# Power.net
KiCad netlist of a schematic drawn in Altium Designer
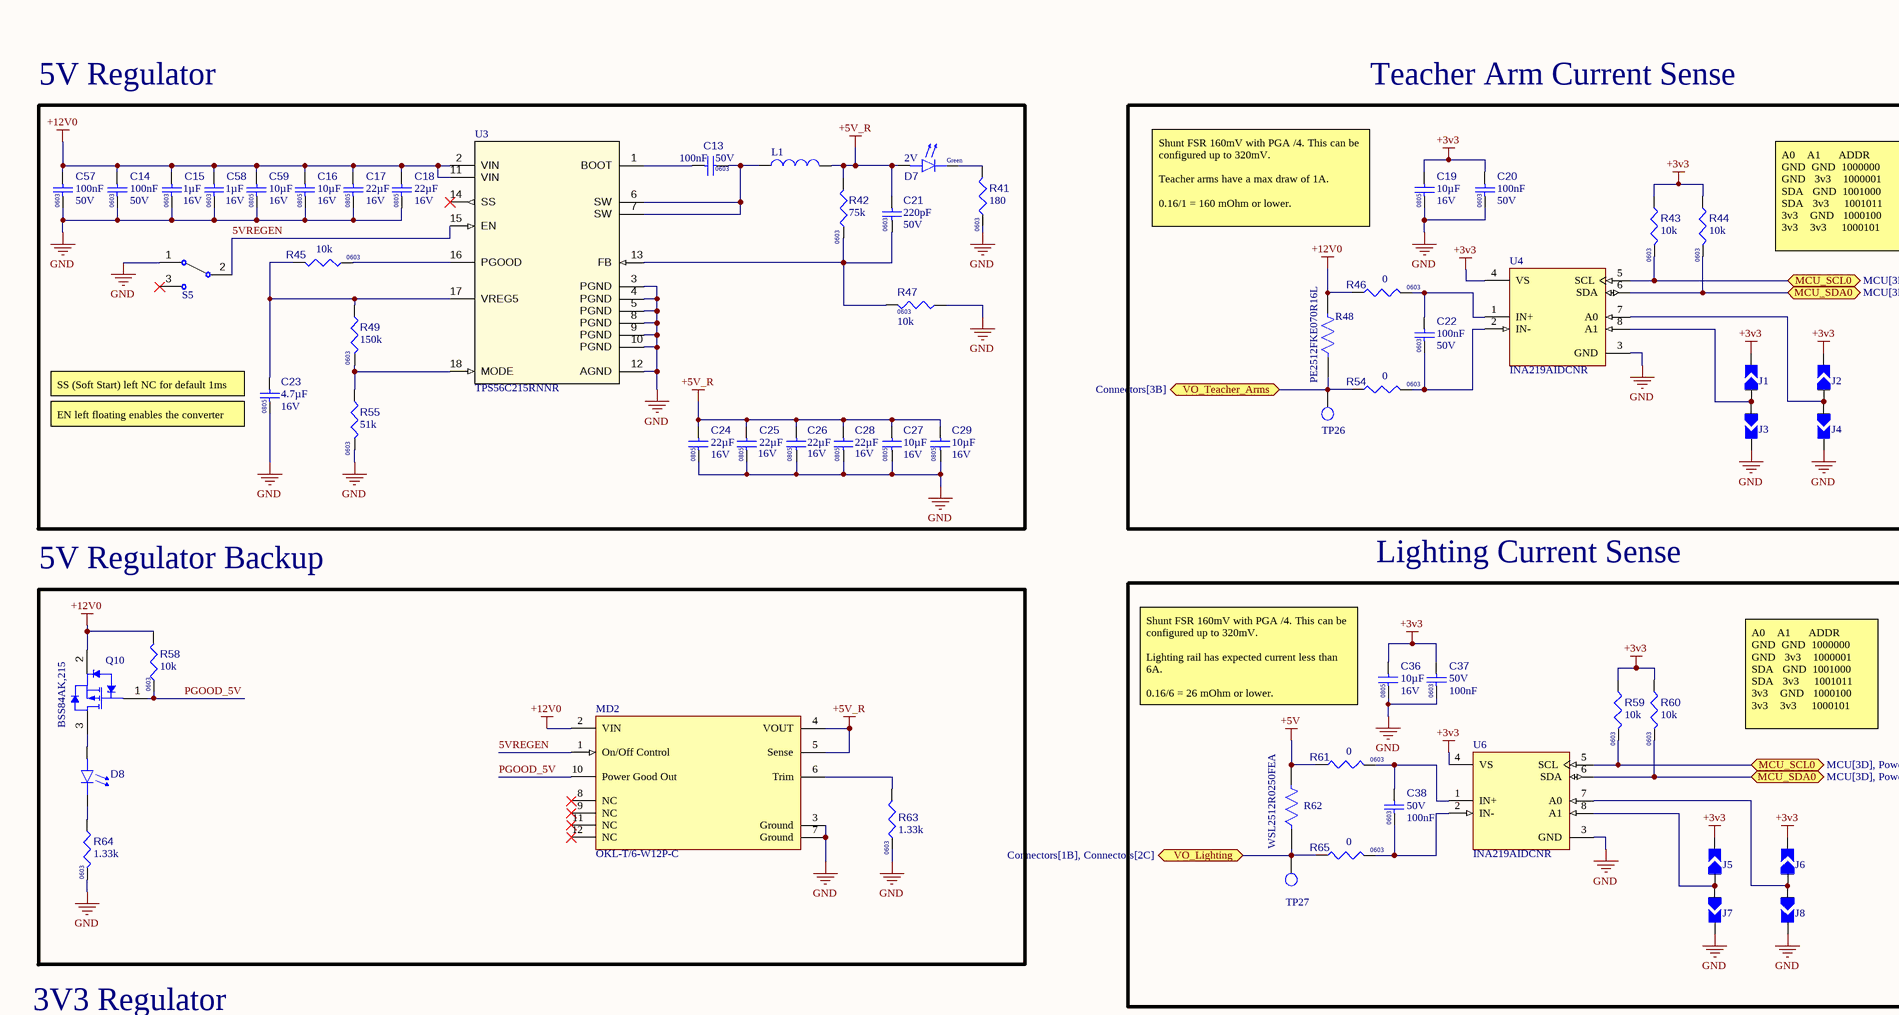
[diagram p0: Power.SchDoc, top left]
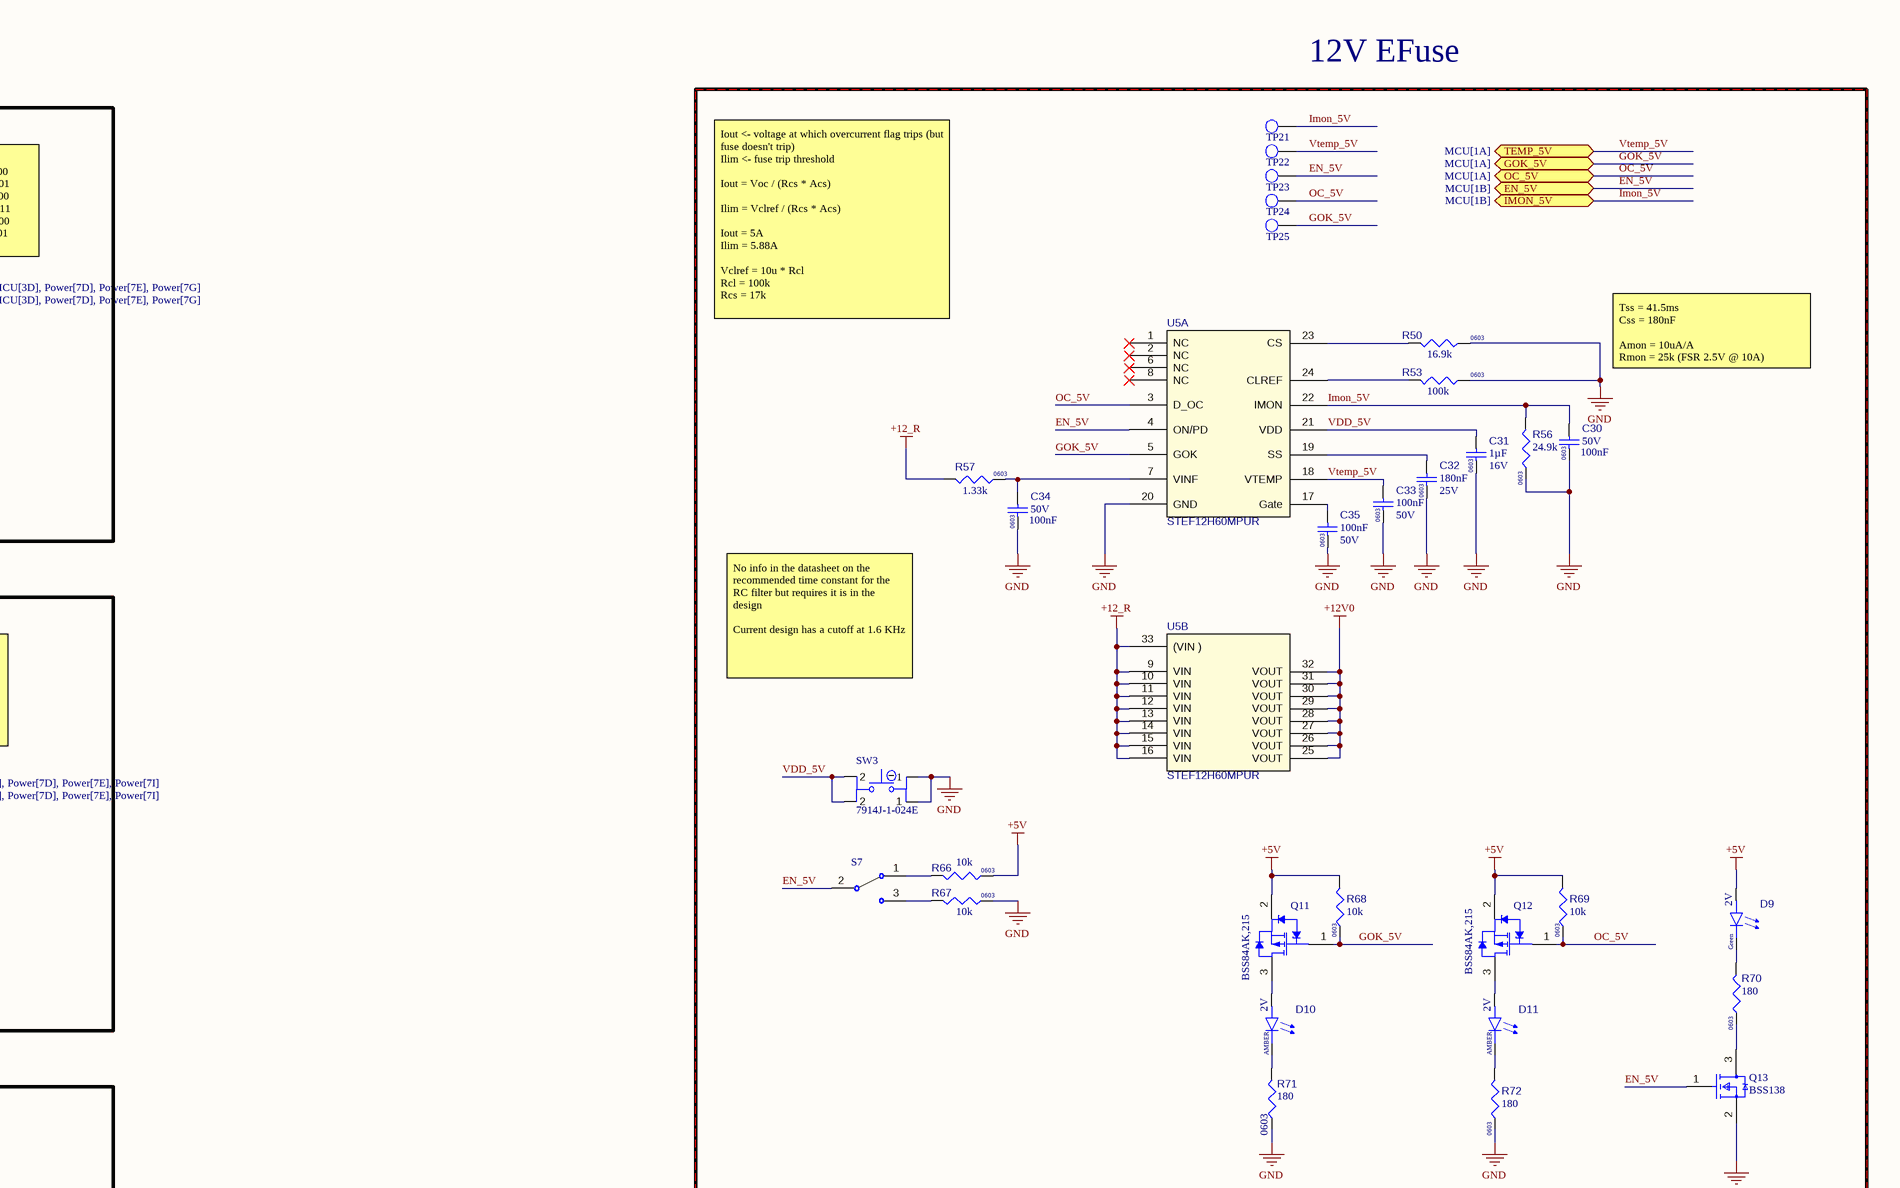
[diagram p1: Power.SchDoc, top right]
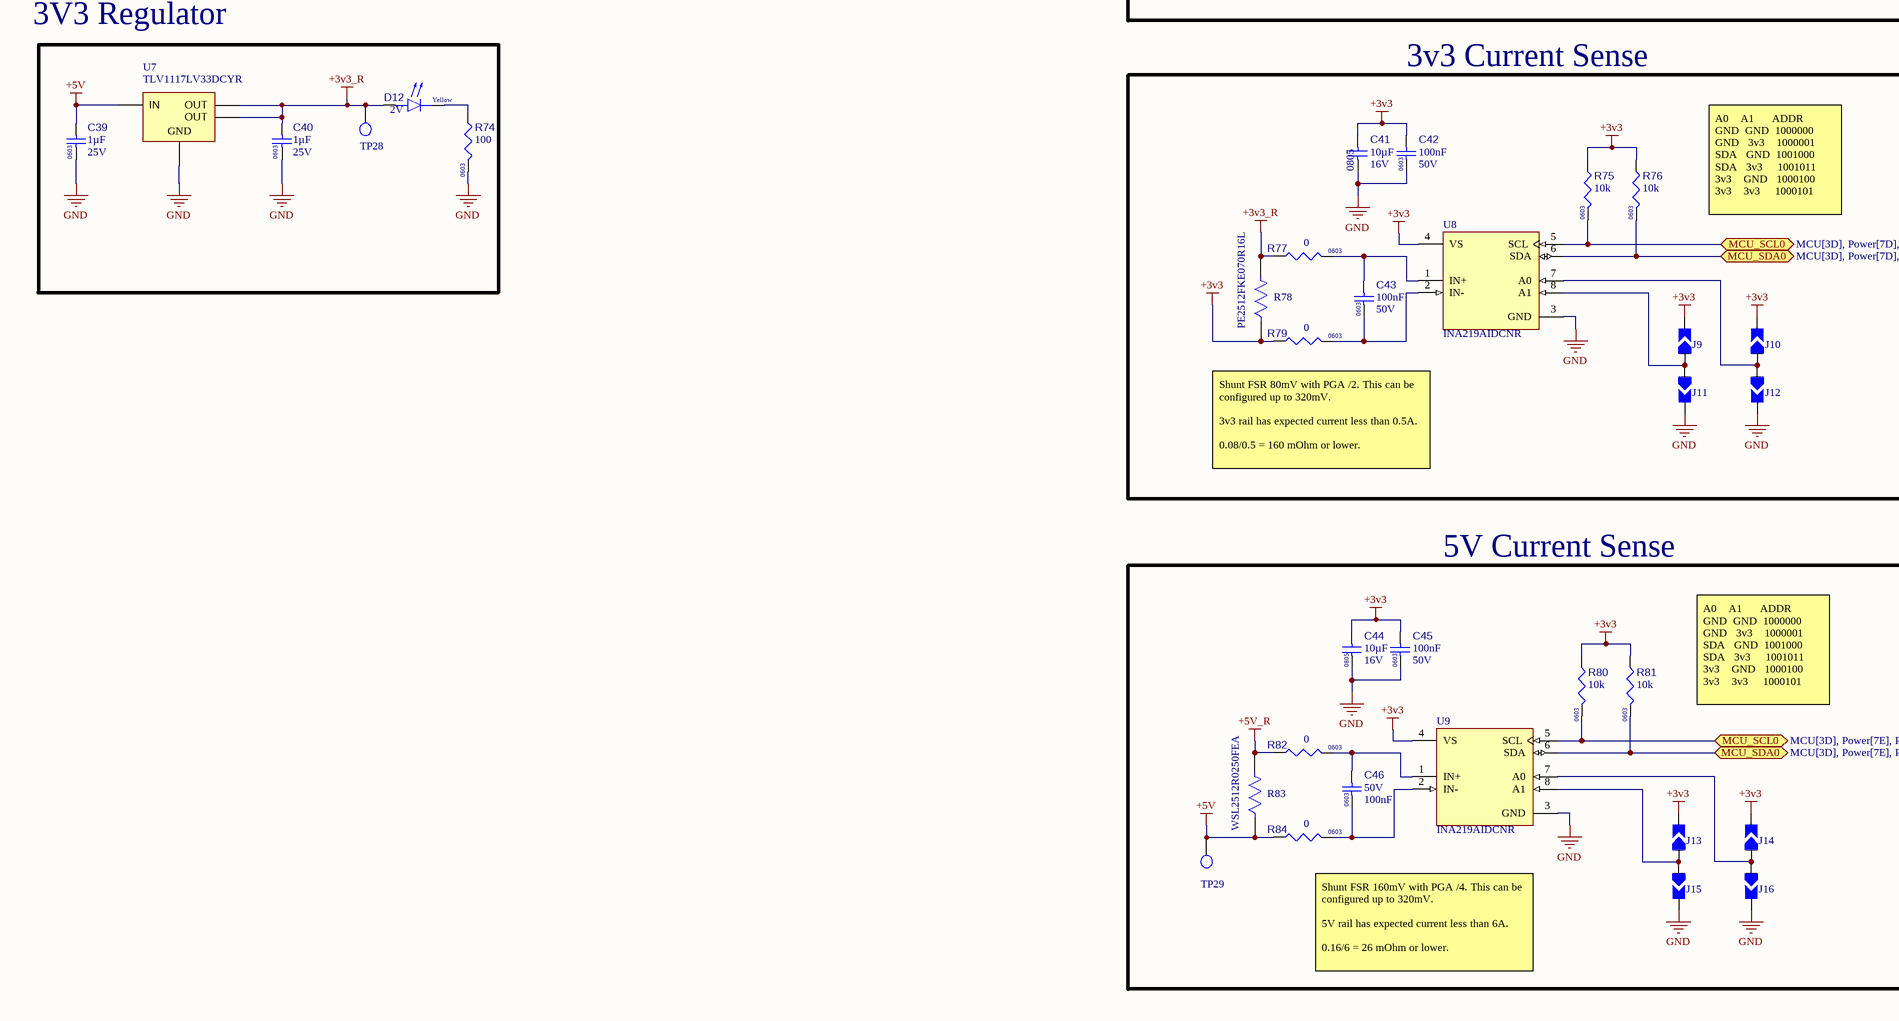
[diagram p2: Power.SchDoc, bottom left]

(export (version "E")
  (design (tool "Eeschema 10.0.6"))
  (components
    (comp (ref "C13")
      (value "100nF")
      (footprint "CAPC1608X90X40NL10T20")
      (description "Chip Capacitor, 100 nF, +/- 10%, 50 V, 0603 (1608 Metric)")
      (fields
        (field (name "TOLERANCE") "10%")
        (field (name "VOLTAGE RATING") "50V")
        (field (name "CASE/PACKAGE") "0603")
        (field (name "Comment") "Capacitor 100 nF +/-10% 50 V 0603")
      )
      (libsource (lib "hawaiirobotics") (part "CAP-NP-2"))
    )
    (comp (ref "C14")
      (value "100nF")
      (footprint "CAPC1608X90X40NL10T20")
      (description "Chip Capacitor, 100 nF, +/- 10%, 50 V, 0603 (1608 Metric)")
      (fields
        (field (name "TOLERANCE") "10%")
        (field (name "VOLTAGE RATING") "50V")
        (field (name "CASE/PACKAGE") "0603")
        (field (name "Comment") "Capacitor 100 nF +/-10% 50 V 0603")
      )
      (libsource (lib "hawaiirobotics") (part "CAP-NP-2"))
    )
    (comp (ref "C15")
      (value "1µF")
      (footprint "CAPC1608X90X35NL15T15")
      (description "Chip Capacitor, 1 uF, +/- 10%, 16 V, 0603 (1608 Metric)")
      (fields
        (field (name "CASE/PACKAGE") "0603")
        (field (name "VOLTAGE RATING") "16V")
        (field (name "TOLERANCE") "10%")
        (field (name "Comment") "Capacitor 1uF +/- 10% 16V 0603")
      )
      (libsource (lib "hawaiirobotics") (part "CAP-NP-2"))
    )
    (comp (ref "C16")
      (value "10µF")
      (footprint "CAP CER 10UF 16V X5R 0805-Footprint-1")
      (fields
        (field (name "VOLTAGE RATING") "16V")
        (field (name "CASE/PACKAGE") "0805")
        (field (name "Comment") "CAP CER 10UF 16V X5R 0805")
      )
      (libsource (lib "hawaiirobotics") (part "CAP-NP-2"))
    )
    (comp (ref "C17")
      (value "22µF")
      (footprint "CL21A226MOQNNNE-Footprint-1")
      (fields
        (field (name "VOLTAGE RATING") "16V")
        (field (name "CASE/PACKAGE") "0805")
        (field (name "Comment") "CL21A226MOQNNNE")
      )
      (libsource (lib "hawaiirobotics") (part "CAP-NP-2"))
    )
    (comp (ref "C18")
      (value "22µF")
      (footprint "CL21A226MOQNNNE-Footprint-1")
      (fields
        (field (name "VOLTAGE RATING") "16V")
        (field (name "CASE/PACKAGE") "0805")
        (field (name "Comment") "CL21A226MOQNNNE")
      )
      (libsource (lib "hawaiirobotics") (part "CAP-NP-2"))
    )
    (comp (ref "C19")
      (value "10µF")
      (footprint "CAP CER 10UF 16V X5R 0805-Footprint-1")
      (fields
        (field (name "VOLTAGE RATING") "16V")
        (field (name "CASE/PACKAGE") "0805")
        (field (name "Comment") "CAP CER 10UF 16V X5R 0805")
      )
      (libsource (lib "hawaiirobotics") (part "CAP-NP-2"))
    )
    (comp (ref "C20")
      (value "100nF")
      (footprint "CAPC1608X90X40NL10T20")
      (description "Chip Capacitor, 100 nF, +/- 10%, 50 V, 0603 (1608 Metric)")
      (fields
        (field (name "TOLERANCE") "10%")
        (field (name "VOLTAGE RATING") "50V")
        (field (name "CASE/PACKAGE") "0603")
        (field (name "Comment") "Capacitor 100 nF +/-10% 50 V 0603")
      )
      (libsource (lib "hawaiirobotics") (part "CAP-NP-2"))
    )
    (comp (ref "C21")
      (value "220pF")
      (footprint "FP-CL10-IPC_B")
      (fields
        (field (name "RATED DC VOLTAGE (URDC)") "50V")
        (field (name "CASE/PACKAGE") "0603")
        (field (name "Comment") "CL10C221JB8NNNC")
      )
      (libsource (lib "hawaiirobotics") (part "CAP-NP-2"))
    )
    (comp (ref "C22")
      (value "100nF")
      (footprint "CAPC1608X90X40NL10T20")
      (description "Chip Capacitor, 100 nF, +/- 10%, 50 V, 0603 (1608 Metric)")
      (fields
        (field (name "TOLERANCE") "10%")
        (field (name "VOLTAGE RATING") "50V")
        (field (name "CASE/PACKAGE") "0603")
        (field (name "Comment") "Capacitor 100 nF +/-10% 50 V 0603")
      )
      (libsource (lib "hawaiirobotics") (part "CAP-NP-2"))
    )
    (comp (ref "C23")
      (value "4.7µF")
      (footprint "CL21A475KOFNNNE-Footprint-1")
      (fields
        (field (name "CASE/PACKAGE") "0805")
        (field (name "RATED DC VOLTAGE (URDC)") "16V")
        (field (name "Comment") "CL21A475KOFNNNE")
      )
      (libsource (lib "hawaiirobotics") (part "CAP-NP-2"))
    )
    (comp (ref "C24")
      (value "22µF")
      (footprint "CL21A226MOQNNNE-Footprint-1")
      (fields
        (field (name "VOLTAGE RATING") "16V")
        (field (name "CASE/PACKAGE") "0805")
        (field (name "Comment") "CL21A226MOQNNNE")
      )
      (libsource (lib "hawaiirobotics") (part "CAP-NP-2"))
    )
    (comp (ref "C25")
      (value "22µF")
      (footprint "CL21A226MOQNNNE-Footprint-1")
      (fields
        (field (name "VOLTAGE RATING") "16V")
        (field (name "CASE/PACKAGE") "0805")
        (field (name "Comment") "CL21A226MOQNNNE")
      )
      (libsource (lib "hawaiirobotics") (part "CAP-NP-2"))
    )
    (comp (ref "C26")
      (value "22µF")
      (footprint "CL21A226MOQNNNE-Footprint-1")
      (fields
        (field (name "VOLTAGE RATING") "16V")
        (field (name "CASE/PACKAGE") "0805")
        (field (name "Comment") "CL21A226MOQNNNE")
      )
      (libsource (lib "hawaiirobotics") (part "CAP-NP-2"))
    )
    (comp (ref "C27")
      (value "10µF")
      (footprint "CAP CER 10UF 16V X5R 0805-Footprint-1")
      (fields
        (field (name "VOLTAGE RATING") "16V")
        (field (name "CASE/PACKAGE") "0805")
        (field (name "Comment") "CAP CER 10UF 16V X5R 0805")
      )
      (libsource (lib "hawaiirobotics") (part "CAP-NP-2"))
    )
    (comp (ref "C28")
      (value "22µF")
      (footprint "CL21A226MOQNNNE-Footprint-1")
      (fields
        (field (name "VOLTAGE RATING") "16V")
        (field (name "CASE/PACKAGE") "0805")
        (field (name "Comment") "CL21A226MOQNNNE")
      )
      (libsource (lib "hawaiirobotics") (part "CAP-NP-2"))
    )
    (comp (ref "C29")
      (value "10µF")
      (footprint "CAP CER 10UF 16V X5R 0805-Footprint-1")
      (fields
        (field (name "VOLTAGE RATING") "16V")
        (field (name "CASE/PACKAGE") "0805")
        (field (name "Comment") "CAP CER 10UF 16V X5R 0805")
      )
      (libsource (lib "hawaiirobotics") (part "CAP-NP-2"))
    )
    (comp (ref "C30")
      (value "100nF")
      (footprint "CAPC1608X90X40NL10T20")
      (description "Chip Capacitor, 100 nF, +/- 10%, 50 V, 0603 (1608 Metric)")
      (fields
        (field (name "TOLERANCE") "10%")
        (field (name "VOLTAGE RATING") "50V")
        (field (name "CASE/PACKAGE") "0603")
        (field (name "Comment") "Capacitor 100 nF +/-10% 50 V 0603")
      )
      (libsource (lib "hawaiirobotics") (part "CAP-NP-2"))
    )
    (comp (ref "C31")
      (value "1µF")
      (footprint "CAPC1608X90X35NL15T15")
      (description "Chip Capacitor, 1 uF, +/- 10%, 16 V, 0603 (1608 Metric)")
      (fields
        (field (name "CASE/PACKAGE") "0603")
        (field (name "TOLERANCE") "10%")
        (field (name "VOLTAGE RATING") "16V")
        (field (name "Comment") "Capacitor 1uF +/- 10% 16V 0603")
      )
      (libsource (lib "hawaiirobotics") (part "CAP-NP-2"))
    )
    (comp (ref "C32")
      (value "180nF")
      (footprint "FP-GCM188-0_1-IPC_C")
      (fields
        (field (name "CASE/PACKAGE") "0603")
        (field (name "RATED DC VOLTAGE (URDC)") "25V")
        (field (name "Comment") "GCM188R71E184KA55D")
      )
      (libsource (lib "hawaiirobotics") (part "CAP-NP-2"))
    )
    (comp (ref "C33")
      (value "100nF")
      (footprint "CAPC1608X90X40NL10T20")
      (description "Chip Capacitor, 100 nF, +/- 10%, 50 V, 0603 (1608 Metric)")
      (fields
        (field (name "TOLERANCE") "10%")
        (field (name "VOLTAGE RATING") "50V")
        (field (name "CASE/PACKAGE") "0603")
        (field (name "Comment") "Capacitor 100 nF +/-10% 50 V 0603")
      )
      (libsource (lib "hawaiirobotics") (part "CAP-NP-2"))
    )
    (comp (ref "C34")
      (value "100nF")
      (footprint "CAPC1608X90X40NL10T20")
      (description "Chip Capacitor, 100 nF, +/- 10%, 50 V, 0603 (1608 Metric)")
      (fields
        (field (name "TOLERANCE") "10%")
        (field (name "VOLTAGE RATING") "50V")
        (field (name "CASE/PACKAGE") "0603")
        (field (name "Comment") "Capacitor 100 nF +/-10% 50 V 0603")
      )
      (libsource (lib "hawaiirobotics") (part "CAP-NP-2"))
    )
    (comp (ref "C35")
      (value "100nF")
      (footprint "CAPC1608X90X40NL10T20")
      (description "Chip Capacitor, 100 nF, +/- 10%, 50 V, 0603 (1608 Metric)")
      (fields
        (field (name "TOLERANCE") "10%")
        (field (name "VOLTAGE RATING") "50V")
        (field (name "CASE/PACKAGE") "0603")
        (field (name "Comment") "Capacitor 100 nF +/-10% 50 V 0603")
      )
      (libsource (lib "hawaiirobotics") (part "CAP-NP-2"))
    )
    (comp (ref "C36")
      (value "10µF")
      (footprint "CAP CER 10UF 16V X5R 0805-Footprint-1")
      (fields
        (field (name "VOLTAGE RATING") "16V")
        (field (name "CASE/PACKAGE") "0805")
        (field (name "Comment") "CAP CER 10UF 16V X5R 0805")
      )
      (libsource (lib "hawaiirobotics") (part "CAP-NP-2"))
    )
    (comp (ref "C37")
      (value "100nF")
      (footprint "CAPC1608X90X40NL10T20")
      (description "Chip Capacitor, 100 nF, +/- 10%, 50 V, 0603 (1608 Metric)")
      (fields
        (field (name "TOLERANCE") "10%")
        (field (name "VOLTAGE RATING") "50V")
        (field (name "CASE/PACKAGE") "0603")
        (field (name "Comment") "Capacitor 100 nF +/-10% 50 V 0603")
      )
      (libsource (lib "hawaiirobotics") (part "CAP-NP-2"))
    )
    (comp (ref "C38")
      (value "100nF")
      (footprint "CAPC1608X90X40NL10T20")
      (description "Chip Capacitor, 100 nF, +/- 10%, 50 V, 0603 (1608 Metric)")
      (fields
        (field (name "TOLERANCE") "10%")
        (field (name "VOLTAGE RATING") "50V")
        (field (name "CASE/PACKAGE") "0603")
        (field (name "Comment") "Capacitor 100 nF +/-10% 50 V 0603")
      )
      (libsource (lib "hawaiirobotics") (part "CAP-NP-2"))
    )
    (comp (ref "C39")
      (value "1µF")
      (footprint "FP-CL10-IPC_B")
      (fields
        (field (name "RATED DC VOLTAGE (URDC)") "25V")
        (field (name "CASE/PACKAGE") "0603")
        (field (name "Comment") "CL10B105KA8NNNC")
      )
      (libsource (lib "hawaiirobotics") (part "CAP-NP-2"))
    )
    (comp (ref "C40")
      (value "1µF")
      (footprint "FP-CL10-IPC_B")
      (fields
        (field (name "RATED DC VOLTAGE (URDC)") "25V")
        (field (name "CASE/PACKAGE") "0603")
        (field (name "Comment") "CL10B105KA8NNNC")
      )
      (libsource (lib "hawaiirobotics") (part "CAP-NP-2"))
    )
    (comp (ref "C41")
      (value "10µF")
      (footprint "CAP CER 10UF 16V X5R 0805-Footprint-1")
      (fields
        (field (name "VOLTAGE RATING") "16V")
        (field (name "CASE/PACKAGE") "0805")
        (field (name "Comment") "CAP CER 10UF 16V X5R 0805")
      )
      (libsource (lib "hawaiirobotics") (part "CAP-NP-2"))
    )
    (comp (ref "C42")
      (value "100nF")
      (footprint "CAPC1608X90X40NL10T20")
      (description "Chip Capacitor, 100 nF, +/- 10%, 50 V, 0603 (1608 Metric)")
      (fields
        (field (name "TOLERANCE") "10%")
        (field (name "VOLTAGE RATING") "50V")
        (field (name "CASE/PACKAGE") "0603")
        (field (name "Comment") "Capacitor 100 nF +/-10% 50 V 0603")
      )
      (libsource (lib "hawaiirobotics") (part "CAP-NP-2"))
    )
    (comp (ref "C43")
      (value "100nF")
      (footprint "CAPC1608X90X40NL10T20")
      (description "Chip Capacitor, 100 nF, +/- 10%, 50 V, 0603 (1608 Metric)")
      (fields
        (field (name "TOLERANCE") "10%")
        (field (name "VOLTAGE RATING") "50V")
        (field (name "CASE/PACKAGE") "0603")
        (field (name "Comment") "Capacitor 100 nF +/-10% 50 V 0603")
      )
      (libsource (lib "hawaiirobotics") (part "CAP-NP-2"))
    )
    (comp (ref "C44")
      (value "10µF")
      (footprint "CAP CER 10UF 16V X5R 0805-Footprint-1")
      (fields
        (field (name "VOLTAGE RATING") "16V")
        (field (name "CASE/PACKAGE") "0805")
        (field (name "Comment") "CAP CER 10UF 16V X5R 0805")
      )
      (libsource (lib "hawaiirobotics") (part "CAP-NP-2"))
    )
    (comp (ref "C45")
      (value "100nF")
      (footprint "CAPC1608X90X40NL10T20")
      (description "Chip Capacitor, 100 nF, +/- 10%, 50 V, 0603 (1608 Metric)")
      (fields
        (field (name "TOLERANCE") "10%")
        (field (name "VOLTAGE RATING") "50V")
        (field (name "CASE/PACKAGE") "0603")
        (field (name "Comment") "Capacitor 100 nF +/-10% 50 V 0603")
      )
      (libsource (lib "hawaiirobotics") (part "CAP-NP-2"))
    )
    (comp (ref "C46")
      (value "100nF")
      (footprint "CAPC1608X90X40NL10T20")
      (description "Chip Capacitor, 100 nF, +/- 10%, 50 V, 0603 (1608 Metric)")
      (fields
        (field (name "TOLERANCE") "10%")
        (field (name "VOLTAGE RATING") "50V")
        (field (name "CASE/PACKAGE") "0603")
        (field (name "Comment") "Capacitor 100 nF +/-10% 50 V 0603")
      )
      (libsource (lib "hawaiirobotics") (part "CAP-NP-2"))
    )
    (comp (ref "C57")
      (value "100nF")
      (footprint "CAPC1608X90X40NL10T20")
      (description "Chip Capacitor, 100 nF, +/- 10%, 50 V, 0603 (1608 Metric)")
      (fields
        (field (name "TOLERANCE") "10%")
        (field (name "VOLTAGE RATING") "50V")
        (field (name "CASE/PACKAGE") "0603")
        (field (name "Comment") "Capacitor 100 nF +/-10% 50 V 0603")
      )
      (libsource (lib "hawaiirobotics") (part "CAP-NP-2"))
    )
    (comp (ref "C58")
      (value "1µF")
      (footprint "CAPC1608X90X35NL15T15")
      (description "Chip Capacitor, 1 uF, +/- 10%, 16 V, 0603 (1608 Metric)")
      (fields
        (field (name "CASE/PACKAGE") "0603")
        (field (name "VOLTAGE RATING") "16V")
        (field (name "TOLERANCE") "10%")
        (field (name "Comment") "Capacitor 1uF +/- 10% 16V 0603")
      )
      (libsource (lib "hawaiirobotics") (part "CAP-NP-2"))
    )
    (comp (ref "C59")
      (value "10µF")
      (footprint "CAP CER 10UF 16V X5R 0805-Footprint-1")
      (fields
        (field (name "VOLTAGE RATING") "16V")
        (field (name "CASE/PACKAGE") "0805")
        (field (name "Comment") "CAP CER 10UF 16V X5R 0805")
      )
      (libsource (lib "hawaiirobotics") (part "CAP-NP-2"))
    )
    (comp (ref "D7")
      (value "150060VS75000")
      (footprint "WL-SMCW_0603_150060xx75000")
      (description "Single Color LED, Bright Green, Water Clear, 1.1mm")
      (fields (field (name "FORWARD VOLTAGE") "2V") (field (name "COLOR") "Green"))
      (libsource (lib "hawaiirobotics") (part "DIODE-LED-2"))
    )
    (comp (ref "D8")
      (value "150060RS75000")
      (footprint "WL-SMCW_0603_150060xx75000")
      (description "Single Color LED, Red, Water Clear, 1.1mm")
      (libsource (lib "hawaiirobotics") (part "DIODE-LED-2"))
    )
    (comp (ref "D9")
      (value "150060VS75000")
      (footprint "WL-SMCW_0603_150060xx75000")
      (description "Single Color LED, Bright Green, Water Clear, 1.1mm")
      (fields (field (name "FORWARD VOLTAGE") "2V") (field (name "COLOR") "Green"))
      (libsource (lib "hawaiirobotics") (part "DIODE-LED-2"))
    )
    (comp (ref "D10")
      (value "150060AS75000")
      (footprint "WL-SMCW_0603_150060xx75000")
      (description "Single Color LED, Amber, Water Clear, 1.1mm")
      (fields (field (name "FORWARD VOLTAGE") "2V") (field (name "COLOUR") "AMBER"))
      (libsource (lib "hawaiirobotics") (part "DIODE-LED-2"))
    )
    (comp (ref "D11")
      (value "150060AS75000")
      (footprint "WL-SMCW_0603_150060xx75000")
      (description "Single Color LED, Amber, Water Clear, 1.1mm")
      (fields (field (name "FORWARD VOLTAGE") "2V") (field (name "COLOUR") "AMBER"))
      (libsource (lib "hawaiirobotics") (part "DIODE-LED-2"))
    )
    (comp (ref "D12")
      (value "150060YS75000")
      (footprint "WL-SMCW_0603_150060xx75000")
      (description "Single Color LED, Yellow, Water Clear, 1.1mm")
      (fields (field (name "FORWARD VOLTAGE") "2V") (field (name "COLOR") "Yellow"))
      (libsource (lib "hawaiirobotics") (part "DIODE-LED-2"))
    )
    (comp (ref "J1")
      (value "Solder jumper")
      (footprint "New footprint 1")
      (libsource (lib "hawaiirobotics") (part "New symbol 1"))
    )
    (comp (ref "J2")
      (value "Solder jumper")
      (footprint "New footprint 1")
      (libsource (lib "hawaiirobotics") (part "New symbol 1"))
    )
    (comp (ref "J3")
      (value "Solder jumper")
      (footprint "New footprint 1")
      (libsource (lib "hawaiirobotics") (part "New symbol 1"))
    )
    (comp (ref "J4")
      (value "Solder jumper")
      (footprint "New footprint 1")
      (libsource (lib "hawaiirobotics") (part "New symbol 1"))
    )
    (comp (ref "J5")
      (value "Solder jumper")
      (footprint "New footprint 1")
      (libsource (lib "hawaiirobotics") (part "New symbol 1"))
    )
    (comp (ref "J6")
      (value "Solder jumper")
      (footprint "New footprint 1")
      (libsource (lib "hawaiirobotics") (part "New symbol 1"))
    )
    (comp (ref "J7")
      (value "Solder jumper")
      (footprint "New footprint 1")
      (libsource (lib "hawaiirobotics") (part "New symbol 1"))
    )
    (comp (ref "J8")
      (value "Solder jumper")
      (footprint "New footprint 1")
      (libsource (lib "hawaiirobotics") (part "New symbol 1"))
    )
    (comp (ref "J9")
      (value "Solder jumper")
      (footprint "New footprint 1")
      (libsource (lib "hawaiirobotics") (part "New symbol 1"))
    )
    (comp (ref "J10")
      (value "Solder jumper")
      (footprint "New footprint 1")
      (libsource (lib "hawaiirobotics") (part "New symbol 1"))
    )
    (comp (ref "J11")
      (value "Solder jumper")
      (footprint "New footprint 1")
      (libsource (lib "hawaiirobotics") (part "New symbol 1"))
    )
    (comp (ref "J12")
      (value "Solder jumper")
      (footprint "New footprint 1")
      (libsource (lib "hawaiirobotics") (part "New symbol 1"))
    )
    (comp (ref "J13")
      (value "Solder jumper")
      (footprint "New footprint 1")
      (libsource (lib "hawaiirobotics") (part "New symbol 1"))
    )
    (comp (ref "J14")
      (value "Solder jumper")
      (footprint "New footprint 1")
      (libsource (lib "hawaiirobotics") (part "New symbol 1"))
    )
    (comp (ref "J15")
      (value "Solder jumper")
      (footprint "New footprint 1")
      (libsource (lib "hawaiirobotics") (part "New symbol 1"))
    )
    (comp (ref "J16")
      (value "Solder jumper")
      (footprint "New footprint 1")
      (libsource (lib "hawaiirobotics") (part "New symbol 1"))
    )
    (comp (ref "L1")
      (value "744325330")
      (footprint "WE-HCI_1050")
      (description "General Purpose Inductor, 3.3uH, 20%, 1 Element, SMD, 4140")
      (fields (field (name "TOLERANCE") "20%"))
      (libsource (lib "hawaiirobotics") (part "IND-2"))
    )
    (comp (ref "MD2")
      (value "OKL-T/6-W12P-C")
      (footprint "FP-OKL-T-6-W12-MFG")
      (description "DC DC CONVERTER 0.591-5.5V 30W")
      (libsource (lib "Altium Content Vault") (part "54782e8334bb74e7d5378ece10d419b"))
    )
    (comp (ref "Q10")
      (value "BSS84AK,215")
      (footprint "NXP-SOT23_N")
      (description "P-Channel Trench MOSFET, -50 V, -0.18 A, -55 to 150 degC, 3-Pin SOT23, Tape and Reel")
      (fields (field (name "MANUFACTURER") "NXP Semiconductors"))
      (libsource (lib "Altium Content Vault") (part "NXP-PMOS-GSD-3_B"))
    )
    (comp (ref "Q11")
      (value "BSS84AK,215")
      (footprint "NXP-SOT23_N")
      (description "P-Channel Trench MOSFET, -50 V, -0.18 A, -55 to 150 degC, 3-Pin SOT23, Tape and Reel")
      (fields (field (name "MANUFACTURER") "NXP Semiconductors"))
      (libsource (lib "Altium Content Vault") (part "NXP-PMOS-GSD-3_B"))
    )
    (comp (ref "Q12")
      (value "BSS84AK,215")
      (footprint "NXP-SOT23_N")
      (description "P-Channel Trench MOSFET, -50 V, -0.18 A, -55 to 150 degC, 3-Pin SOT23, Tape and Reel")
      (fields (field (name "MANUFACTURER") "NXP Semiconductors"))
      (libsource (lib "Altium Content Vault") (part "NXP-PMOS-GSD-3_B"))
    )
    (comp (ref "Q13")
      (value "BSS138")
      (footprint "FP-318-08-IPC_B")
      (description "MOSFET N-CH 50V 220MA SOT-23")
      (libsource (lib "Altium Content Vault") (part "3b9c635fedb024a5347a57b145af9cc"))
    )
    (comp (ref "R41")
      (value "180")
      (footprint "RESC0603(1608)_N")
      (fields
        (field (name "TOLERANCE") "5%")
        (field (name "CASE/PACKAGE") "0603")
        (field (name "POWER") "100mW")
        (field (name "Comment") "RC0603JR-07180RL")
      )
      (libsource (lib "hawaiirobotics") (part "RES-2"))
    )
    (comp (ref "R42")
      (value "75k")
      (footprint "RC0603JR-0720KL-Footprint-1")
      (fields
        (field (name "TOLERANCE") "1%")
        (field (name "POWER") "100mW")
        (field (name "CASE/PACKAGE") "0603")
        (field (name "Comment") "RC0603FR-0775KL")
      )
      (libsource (lib "hawaiirobotics") (part "RES-2"))
    )
    (comp (ref "R43")
      (value "10k")
      (footprint "RESC1608X55X25NL10T15")
      (description "Chip Resistor, 10 KOhm, +/- 1%, 01 W, -55 to 155 degC, 0603 (1608 Metric)")
      (fields
        (field (name "CASE/PACKAGE") "0603")
        (field (name "POWER") "100mW")
        (field (name "TOLERANCE") "1%")
      )
      (libsource (lib "hawaiirobotics") (part "RES-2"))
    )
    (comp (ref "R44")
      (value "10k")
      (footprint "RESC1608X55X25NL10T15")
      (description "Chip Resistor, 10 KOhm, +/- 1%, 01 W, -55 to 155 degC, 0603 (1608 Metric)")
      (fields
        (field (name "CASE/PACKAGE") "0603")
        (field (name "POWER") "100mW")
        (field (name "TOLERANCE") "1%")
      )
      (libsource (lib "hawaiirobotics") (part "RES-2"))
    )
    (comp (ref "R45")
      (value "10k")
      (footprint "RESC1608X55X25NL10T15")
      (description "Chip Resistor, 10 KOhm, +/- 1%, 01 W, -55 to 155 degC, 0603 (1608 Metric)")
      (fields
        (field (name "CASE/PACKAGE") "0603")
        (field (name "POWER") "100mW")
        (field (name "TOLERANCE") "1%")
      )
      (libsource (lib "hawaiirobotics") (part "RES-2"))
    )
    (comp (ref "R46")
      (value "0")
      (footprint "RC0603JR-0720KL-Footprint-1")
      (description "Metal Glaze/thick Film, 0.1W, 0ohm, Surface Mount, 0603")
      (fields
        (field (name "CASE/PACKAGE") "0603")
        (field (name "TOLERANCE") "1%")
        (field (name "POWER") "100mW")
      )
      (libsource (lib "hawaiirobotics") (part "RES-2"))
    )
    (comp (ref "R47")
      (value "10k")
      (footprint "RESC1608X55X25NL10T15")
      (description "Chip Resistor, 10 KOhm, +/- 1%, 01 W, -55 to 155 degC, 0603 (1608 Metric)")
      (fields
        (field (name "CASE/PACKAGE") "0603")
        (field (name "POWER") "100mW")
        (field (name "TOLERANCE") "1%")
      )
      (libsource (lib "hawaiirobotics") (part "RES-2"))
    )
    (comp (ref "R48")
      (value "PE2512FKE070R16L")
      (footprint "FP-WSL2512-0_762-IPC_B")
      (description "Resistor Current Sense Metal Film 2512 160mOhm ±1% 1W ±50ppm/°C T/R Automotive")
      (libsource (lib "hawaiirobotics") (part "1029c3af85768c4190bb7ad29bc67b5"))
    )
    (comp (ref "R49")
      (value "150k")
      (footprint "RC0603JR-0720KL-Footprint-1")
      (fields
        (field (name "CASE/PACKAGE") "0603")
        (field (name "TOLERANCE") "1%")
        (field (name "POWER") "100mW")
        (field (name "Comment") "RC0603FR-13150KL")
      )
      (libsource (lib "hawaiirobotics") (part "RES-2"))
    )
    (comp (ref "R50")
      (value "16.9k")
      (footprint "RESC1608X55X25NL10T15")
      (fields
        (field (name "CASE/PACKAGE") "0603")
        (field (name "TOLERANCE") "1%")
        (field (name "POWER") "100mW")
        (field (name "Comment") "RC0603FR-0716K9L")
      )
      (libsource (lib "hawaiirobotics") (part "RES-2"))
    )
    (comp (ref "R53")
      (value "100k")
      (footprint "RESC1608X55X25NL10T15")
      (fields
        (field (name "POWER") "100mW")
        (field (name "TOLERANCE") "1%")
        (field (name "CASE/PACKAGE") "0603")
        (field (name "Comment") "RC0603FR-07100KL")
      )
      (libsource (lib "hawaiirobotics") (part "RES-2"))
    )
    (comp (ref "R54")
      (value "0")
      (footprint "RC0603JR-0720KL-Footprint-1")
      (description "Metal Glaze/thick Film, 0.1W, 0ohm, Surface Mount, 0603")
      (fields
        (field (name "CASE/PACKAGE") "0603")
        (field (name "TOLERANCE") "1%")
        (field (name "POWER") "100mW")
      )
      (libsource (lib "hawaiirobotics") (part "RES-2"))
    )
    (comp (ref "R55")
      (value "51k")
      (footprint "RC0603JR-0720KL-Footprint-1")
      (fields
        (field (name "TOLERANCE") "1%")
        (field (name "CASE/PACKAGE") "0603")
        (field (name "POWER") "100mW")
        (field (name "Comment") "RC0603FR-0751KL")
      )
      (libsource (lib "hawaiirobotics") (part "RES-2"))
    )
    (comp (ref "R56")
      (value "24.9k")
      (footprint "RESC1608X55X25NL10T15")
      (fields
        (field (name "POWER") "100mW")
        (field (name "TOLERANCE") "1%")
        (field (name "CASE/PACKAGE") "0603")
        (field (name "Comment") "RC0603FR-1024K9L")
      )
      (libsource (lib "hawaiirobotics") (part "RES-2"))
    )
    (comp (ref "R57")
      (value "1.33k")
      (footprint "RESC1608X55X25NL10T15")
      (fields
        (field (name "TOLERANCE") "1%")
        (field (name "CASE/PACKAGE") "0603")
        (field (name "POWER") "100mW")
        (field (name "Comment") "RC0603FR-071K33L")
      )
      (libsource (lib "hawaiirobotics") (part "RES-2"))
    )
    (comp (ref "R58")
      (value "10k")
      (footprint "RESC1608X55X25NL10T15")
      (description "Chip Resistor, 10 KOhm, +/- 1%, 01 W, -55 to 155 degC, 0603 (1608 Metric)")
      (fields
        (field (name "CASE/PACKAGE") "0603")
        (field (name "POWER") "100mW")
        (field (name "TOLERANCE") "1%")
      )
      (libsource (lib "hawaiirobotics") (part "RES-2"))
    )
    (comp (ref "R59")
      (value "10k")
      (footprint "RESC1608X55X25NL10T15")
      (description "Chip Resistor, 10 KOhm, +/- 1%, 01 W, -55 to 155 degC, 0603 (1608 Metric)")
      (fields
        (field (name "CASE/PACKAGE") "0603")
        (field (name "POWER") "100mW")
        (field (name "TOLERANCE") "1%")
      )
      (libsource (lib "hawaiirobotics") (part "RES-2"))
    )
    (comp (ref "R60")
      (value "10k")
      (footprint "RESC1608X55X25NL10T15")
      (description "Chip Resistor, 10 KOhm, +/- 1%, 01 W, -55 to 155 degC, 0603 (1608 Metric)")
      (fields
        (field (name "CASE/PACKAGE") "0603")
        (field (name "POWER") "100mW")
        (field (name "TOLERANCE") "1%")
      )
      (libsource (lib "hawaiirobotics") (part "RES-2"))
    )
    (comp (ref "R61")
      (value "0")
      (footprint "RC0603JR-0720KL-Footprint-1")
      (description "Metal Glaze/thick Film, 0.1W, 0ohm, Surface Mount, 0603")
      (fields
        (field (name "CASE/PACKAGE") "0603")
        (field (name "TOLERANCE") "1%")
        (field (name "POWER") "100mW")
      )
      (libsource (lib "hawaiirobotics") (part "RES-2"))
    )
    (comp (ref "R62")
      (value "WSL2512R0250FEA")
      (footprint "FP-WSL2512-0_762-IPC_B")
      (description "Fixed Resistor, Metal Strip, 1W, 0.025ohm, 0.1581V, 1% +/-Tol, 75ppm/Cel, Surface Mount, 2512")
      (libsource (lib "hawaiirobotics") (part "1029c3af85768c4190bb7ad29bc67b5"))
    )
    (comp (ref "R63")
      (value "1.33k")
      (footprint "RESC1608X55X25NL10T15")
      (fields
        (field (name "POWER") "100mW")
        (field (name "TOLERANCE") "1%")
        (field (name "CASE/PACKAGE") "0603")
        (field (name "Comment") "RC0603FR-071K33L")
      )
      (libsource (lib "hawaiirobotics") (part "RES-2"))
    )
    (comp (ref "R64")
      (value "1.33k")
      (footprint "RESC1608X55X25NL10T15")
      (fields
        (field (name "TOLERANCE") "1%")
        (field (name "CASE/PACKAGE") "0603")
        (field (name "POWER") "100mW")
        (field (name "Comment") "RC0603FR-071K33L")
      )
      (libsource (lib "hawaiirobotics") (part "RES-2"))
    )
    (comp (ref "R65")
      (value "0")
      (footprint "RC0603JR-0720KL-Footprint-1")
      (description "Metal Glaze/thick Film, 0.1W, 0ohm, Surface Mount, 0603")
      (fields
        (field (name "CASE/PACKAGE") "0603")
        (field (name "TOLERANCE") "1%")
        (field (name "POWER") "100mW")
      )
      (libsource (lib "hawaiirobotics") (part "RES-2"))
    )
    (comp (ref "R66")
      (value "10k")
      (footprint "RESC1608X55X25NL10T15")
      (description "Chip Resistor, 10 KOhm, +/- 1%, 01 W, -55 to 155 degC, 0603 (1608 Metric)")
      (fields
        (field (name "CASE/PACKAGE") "0603")
        (field (name "POWER") "100mW")
        (field (name "TOLERANCE") "1%")
      )
      (libsource (lib "hawaiirobotics") (part "RES-2"))
    )
    (comp (ref "R67")
      (value "10k")
      (footprint "RESC1608X55X25NL10T15")
      (description "Chip Resistor, 10 KOhm, +/- 1%, 01 W, -55 to 155 degC, 0603 (1608 Metric)")
      (fields
        (field (name "CASE/PACKAGE") "0603")
        (field (name "POWER") "100mW")
        (field (name "TOLERANCE") "1%")
      )
      (libsource (lib "hawaiirobotics") (part "RES-2"))
    )
    (comp (ref "R68")
      (value "10k")
      (footprint "RESC1608X55X25NL10T15")
      (description "Chip Resistor, 10 KOhm, +/- 1%, 01 W, -55 to 155 degC, 0603 (1608 Metric)")
      (fields
        (field (name "CASE/PACKAGE") "0603")
        (field (name "POWER") "100mW")
        (field (name "TOLERANCE") "1%")
      )
      (libsource (lib "hawaiirobotics") (part "RES-2"))
    )
    (comp (ref "R69")
      (value "10k")
      (footprint "RESC1608X55X25NL10T15")
      (description "Chip Resistor, 10 KOhm, +/- 1%, 01 W, -55 to 155 degC, 0603 (1608 Metric)")
      (fields
        (field (name "CASE/PACKAGE") "0603")
        (field (name "POWER") "100mW")
        (field (name "TOLERANCE") "1%")
      )
      (libsource (lib "hawaiirobotics") (part "RES-2"))
    )
    (comp (ref "R70")
      (value "180")
      (footprint "RESC0603(1608)_N")
      (fields
        (field (name "TOLERANCE") "5%")
        (field (name "CASE/PACKAGE") "0603")
        (field (name "POWER") "100mW")
        (field (name "Comment") "RC0603JR-07180RL")
      )
      (libsource (lib "hawaiirobotics") (part "RES-2"))
    )
    (comp (ref "R71")
      (value "180")
      (footprint "RESC0603(1608)_N")
      (fields
        (field (name "TOLERANCE") "5%")
        (field (name "CASE/PACKAGE") "0603")
        (field (name "POWER") "100mW")
        (field (name "Comment") "RC0603JR-07180RL")
      )
      (libsource (lib "hawaiirobotics") (part "RES-2"))
    )
    (comp (ref "R72")
      (value "180")
      (footprint "RESC0603(1608)_N")
      (fields
        (field (name "TOLERANCE") "5%")
        (field (name "CASE/PACKAGE") "0603")
        (field (name "POWER") "100mW")
        (field (name "Comment") "RC0603JR-07180RL")
      )
      (libsource (lib "hawaiirobotics") (part "RES-2"))
    )
    (comp (ref "R74")
      (value "100")
      (footprint "RC0603JR-0720KL-Footprint-1")
      (fields
        (field (name "TOLERANCE") "1%")
        (field (name "CASE/PACKAGE") "0603")
        (field (name "POWER") "100mW")
        (field (name "Comment") "RC0603FR-07100RL")
      )
      (libsource (lib "hawaiirobotics") (part "RES-2"))
    )
    (comp (ref "R75")
      (value "10k")
      (footprint "RESC1608X55X25NL10T15")
      (description "Chip Resistor, 10 KOhm, +/- 1%, 01 W, -55 to 155 degC, 0603 (1608 Metric)")
      (fields
        (field (name "CASE/PACKAGE") "0603")
        (field (name "POWER") "100mW")
        (field (name "TOLERANCE") "1%")
      )
      (libsource (lib "hawaiirobotics") (part "RES-2"))
    )
    (comp (ref "R76")
      (value "10k")
      (footprint "RESC1608X55X25NL10T15")
      (description "Chip Resistor, 10 KOhm, +/- 1%, 01 W, -55 to 155 degC, 0603 (1608 Metric)")
      (fields
        (field (name "CASE/PACKAGE") "0603")
        (field (name "POWER") "100mW")
        (field (name "TOLERANCE") "1%")
      )
      (libsource (lib "hawaiirobotics") (part "RES-2"))
    )
    (comp (ref "R77")
      (value "0")
      (footprint "RC0603JR-0720KL-Footprint-1")
      (description "Metal Glaze/thick Film, 0.1W, 0ohm, Surface Mount, 0603")
      (fields
        (field (name "CASE/PACKAGE") "0603")
        (field (name "TOLERANCE") "1%")
        (field (name "POWER") "100mW")
      )
      (libsource (lib "hawaiirobotics") (part "RES-2"))
    )
    (comp (ref "R78")
      (value "PE2512FKE070R16L")
      (footprint "FP-WSL2512-0_762-IPC_B")
      (description "Resistor Current Sense Metal Film 2512 160mOhm ±1% 1W ±50ppm/°C T/R Automotive")
      (libsource (lib "hawaiirobotics") (part "1029c3af85768c4190bb7ad29bc67b5"))
    )
    (comp (ref "R79")
      (value "0")
      (footprint "RC0603JR-0720KL-Footprint-1")
      (description "Metal Glaze/thick Film, 0.1W, 0ohm, Surface Mount, 0603")
      (fields
        (field (name "CASE/PACKAGE") "0603")
        (field (name "TOLERANCE") "1%")
        (field (name "POWER") "100mW")
      )
      (libsource (lib "hawaiirobotics") (part "RES-2"))
    )
    (comp (ref "R80")
      (value "10k")
      (footprint "RESC1608X55X25NL10T15")
      (description "Chip Resistor, 10 KOhm, +/- 1%, 01 W, -55 to 155 degC, 0603 (1608 Metric)")
      (fields
        (field (name "CASE/PACKAGE") "0603")
        (field (name "POWER") "100mW")
        (field (name "TOLERANCE") "1%")
      )
      (libsource (lib "hawaiirobotics") (part "RES-2"))
    )
    (comp (ref "R81")
      (value "10k")
      (footprint "RESC1608X55X25NL10T15")
      (description "Chip Resistor, 10 KOhm, +/- 1%, 01 W, -55 to 155 degC, 0603 (1608 Metric)")
      (fields
        (field (name "CASE/PACKAGE") "0603")
        (field (name "POWER") "100mW")
        (field (name "TOLERANCE") "1%")
      )
      (libsource (lib "hawaiirobotics") (part "RES-2"))
    )
    (comp (ref "R82")
      (value "0")
      (footprint "RC0603JR-0720KL-Footprint-1")
      (description "Metal Glaze/thick Film, 0.1W, 0ohm, Surface Mount, 0603")
      (fields
        (field (name "CASE/PACKAGE") "0603")
        (field (name "TOLERANCE") "1%")
        (field (name "POWER") "100mW")
      )
      (libsource (lib "hawaiirobotics") (part "RES-2"))
    )
    (comp (ref "R83")
      (value "WSL2512R0250FEA")
      (footprint "FP-WSL2512-0_762-IPC_B")
      (description "Fixed Resistor, Metal Strip, 1W, 0.025ohm, 0.1581V, 1% +/-Tol, 75ppm/Cel, Surface Mount, 2512")
      (libsource (lib "hawaiirobotics") (part "1029c3af85768c4190bb7ad29bc67b5"))
    )
    (comp (ref "R84")
      (value "0")
      (footprint "RC0603JR-0720KL-Footprint-1")
      (description "Metal Glaze/thick Film, 0.1W, 0ohm, Surface Mount, 0603")
      (fields
        (field (name "CASE/PACKAGE") "0603")
        (field (name "TOLERANCE") "1%")
        (field (name "POWER") "100mW")
      )
      (libsource (lib "hawaiirobotics") (part "RES-2"))
    )
    (comp (ref "S5")
      (value "SLW-883935-2A-D")
      (footprint "SLW-883935-2A-D-Footprint-1")
      (description "8.8 X 3.9 X 3.5 Mm, 2 Mm Raised")
      (libsource (lib "hawaiirobotics") (part "SLW-883935-2A-D-Symbol-1"))
    )
    (comp (ref "S7")
      (value "SLW-883935-2A-D")
      (footprint "SLW-883935-2A-D-Footprint-1")
      (description "8.8 X 3.9 X 3.5 Mm, 2 Mm Raised")
      (libsource (lib "hawaiirobotics") (part "SLW-883935-2A-D-Symbol-1"))
    )
    (comp (ref "SW3")
      (value "7914J-1-024E")
      (footprint "FP-7914J-1-024E-MFG")
      (libsource (lib "hawaiirobotics") (part "4aa6f850d040344456d32f8cc0a5a85"))
    )
    (comp (ref "TP21")
      (value "RCUCTE")
      (footprint "FP-S2761-46R-MFG")
      (description "Test point")
      (libsource (lib "hawaiirobotics") (part "RCUCTE-Symbol-1"))
    )
    (comp (ref "TP22")
      (value "RCUCTE")
      (footprint "FP-S2761-46R-MFG")
      (description "Test point")
      (libsource (lib "hawaiirobotics") (part "RCUCTE-Symbol-1"))
    )
    (comp (ref "TP23")
      (value "RCUCTE")
      (footprint "FP-S2761-46R-MFG")
      (description "Test point")
      (libsource (lib "hawaiirobotics") (part "RCUCTE-Symbol-1"))
    )
    (comp (ref "TP24")
      (value "RCUCTE")
      (footprint "FP-S2761-46R-MFG")
      (description "Test point")
      (libsource (lib "hawaiirobotics") (part "RCUCTE-Symbol-1"))
    )
    (comp (ref "TP25")
      (value "RCUCTE")
      (footprint "FP-S2761-46R-MFG")
      (description "Test point")
      (libsource (lib "hawaiirobotics") (part "RCUCTE-Symbol-1"))
    )
    (comp (ref "TP26")
      (value "RCUCTE")
      (footprint "FP-S2761-46R-MFG")
      (description "Test point")
      (libsource (lib "hawaiirobotics") (part "RCUCTE-Symbol-1"))
    )
    (comp (ref "TP27")
      (value "RCUCTE")
      (footprint "FP-S2761-46R-MFG")
      (description "Test point")
      (libsource (lib "hawaiirobotics") (part "RCUCTE-Symbol-1"))
    )
    (comp (ref "TP28")
      (value "RCUCTE")
      (footprint "FP-S2761-46R-MFG")
      (description "Test point")
      (libsource (lib "hawaiirobotics") (part "RCUCTE-Symbol-1"))
    )
    (comp (ref "TP29")
      (value "RCUCTE")
      (footprint "FP-S2761-46R-MFG")
      (description "Test point")
      (libsource (lib "hawaiirobotics") (part "RCUCTE-Symbol-1"))
    )
    (comp (ref "U3")
      (value "TPS56C215RNNR")
      (footprint "TPS56C215RNNR-Footprint-1")
      (description "Switching Regulator, 12A, 1200kHz Switching Freq-Max, PQCC18")
      (libsource (lib "hawaiirobotics") (part "TPS56C215RNNR-Symbol-1"))
    )
    (comp (ref "U4")
      (value "INA219AIDCNR")
      (footprint "FP-DCN0008A-IPC_B")
      (description "IC CURRENT MONITOR 1% SOT23-8")
      (libsource (lib "Altium Content Vault") (part "e16934b8ef90d0e345b266f0ae9cd81"))
    )
    (comp (ref "U5")
      (value "STEF12H60MPUR")
      (footprint "STEF12H60MPUR-Footprint-1")
      (description "IC ELECTRONIC FUSE 32QFN")
      (libsource (lib "hawaiirobotics") (part "STEF12H60MPUR"))
    )
    (comp (ref "U6")
      (value "INA219AIDCNR")
      (footprint "FP-DCN0008A-IPC_B")
      (description "IC CURRENT MONITOR 1% SOT23-8")
      (libsource (lib "Altium Content Vault") (part "e16934b8ef90d0e345b266f0ae9cd81"))
    )
    (comp (ref "U7")
      (value "TLV1117LV33DCYR")
      (footprint "DCY0004A_L")
      (description "Fixed Positive LDO Regulator, 3.3V, 0.7V Dropout, CMOS, PDSO4")
      (libsource (lib "hawaiirobotics") (part "TI-TLV1117LV33DCY4"))
    )
    (comp (ref "U8")
      (value "INA219AIDCNR")
      (footprint "FP-DCN0008A-IPC_B")
      (description "IC CURRENT MONITOR 1% SOT23-8")
      (libsource (lib "Altium Content Vault") (part "e16934b8ef90d0e345b266f0ae9cd81"))
    )
    (comp (ref "U9")
      (value "INA219AIDCNR")
      (footprint "FP-DCN0008A-IPC_B")
      (description "IC CURRENT MONITOR 1% SOT23-8")
      (libsource (lib "Altium Content Vault") (part "e16934b8ef90d0e345b266f0ae9cd81"))
    )
  )
  (nets
    (net (code "1") (name "+3v3") (class "Default")
      (node (ref "C19") (pin "2") (pinfunction "2_2") (pintype "passive"))
      (node (ref "C20") (pin "2") (pinfunction "2_2") (pintype "passive"))
      (node (ref "C36") (pin "2") (pinfunction "2_2") (pintype "passive"))
      (node (ref "C37") (pin "2") (pinfunction "2_2") (pintype "passive"))
      (node (ref "C41") (pin "2") (pinfunction "2_2") (pintype "passive"))
      (node (ref "C42") (pin "2") (pinfunction "2_2") (pintype "passive"))
      (node (ref "C44") (pin "2") (pinfunction "2_2") (pintype "passive"))
      (node (ref "C45") (pin "2") (pinfunction "2_2") (pintype "passive"))
      (node (ref "J1") (pin "2") (pinfunction "2_2") (pintype "passive"))
      (node (ref "J10") (pin "2") (pinfunction "2_2") (pintype "passive"))
      (node (ref "J13") (pin "2") (pinfunction "2_2") (pintype "passive"))
      (node (ref "J14") (pin "2") (pinfunction "2_2") (pintype "passive"))
      (node (ref "J2") (pin "2") (pinfunction "2_2") (pintype "passive"))
      (node (ref "J5") (pin "2") (pinfunction "2_2") (pintype "passive"))
      (node (ref "J6") (pin "2") (pinfunction "2_2") (pintype "passive"))
      (node (ref "J9") (pin "2") (pinfunction "2_2") (pintype "passive"))
      (node (ref "R43") (pin "1") (pinfunction "1_1") (pintype "passive"))
      (node (ref "R44") (pin "1") (pinfunction "1_1") (pintype "passive"))
      (node (ref "R59") (pin "1") (pinfunction "1_1") (pintype "passive"))
      (node (ref "R60") (pin "1") (pinfunction "1_1") (pintype "passive"))
      (node (ref "R75") (pin "1") (pinfunction "1_1") (pintype "passive"))
      (node (ref "R76") (pin "1") (pinfunction "1_1") (pintype "passive"))
      (node (ref "R78") (pin "1") (pinfunction "1_1") (pintype "passive"))
      (node (ref "R79") (pin "1") (pinfunction "1_1") (pintype "passive"))
      (node (ref "R80") (pin "1") (pinfunction "1_1") (pintype "passive"))
      (node (ref "R81") (pin "1") (pinfunction "1_1") (pintype "passive"))
      (node (ref "U4") (pin "4") (pinfunction "VS_4") (pintype "power_in"))
      (node (ref "U6") (pin "4") (pinfunction "VS_4") (pintype "power_in"))
      (node (ref "U8") (pin "4") (pinfunction "VS_4") (pintype "power_in"))
      (node (ref "U9") (pin "4") (pinfunction "VS_4") (pintype "power_in"))
    )
    (net (code "2") (name "+3v3_R") (class "Default")
      (node (ref "C40") (pin "2") (pinfunction "2_2") (pintype "passive"))
      (node (ref "D12") (pin "2") (pinfunction "A_2") (pintype "passive"))
      (node (ref "R77") (pin "1") (pinfunction "1_1") (pintype "passive"))
      (node (ref "R78") (pin "2") (pinfunction "2_2") (pintype "passive"))
      (node (ref "TP28") (pin "1") (pinfunction "1_1") (pintype "passive"))
      (node (ref "U7") (pin "2") (pinfunction "OUT_2") (pintype "power_in"))
      (node (ref "U7") (pin "4") (pinfunction "OUT_4") (pintype "power_in"))
    )
    (net (code "3") (name "+5V") (class "Default")
      (node (ref "C39") (pin "2") (pinfunction "2_2") (pintype "passive"))
      (node (ref "D9") (pin "2") (pinfunction "A_2") (pintype "passive"))
      (node (ref "Q11") (pin "2") (pinfunction "S_2") (pintype "passive"))
      (node (ref "Q12") (pin "2") (pinfunction "S_2") (pintype "passive"))
      (node (ref "R61") (pin "1") (pinfunction "1_1") (pintype "passive"))
      (node (ref "R62") (pin "2") (pinfunction "2_2") (pintype "passive"))
      (node (ref "R66") (pin "2") (pinfunction "2_2") (pintype "passive"))
      (node (ref "R68") (pin "2") (pinfunction "2_2") (pintype "passive"))
      (node (ref "R69") (pin "2") (pinfunction "2_2") (pintype "passive"))
      (node (ref "R83") (pin "1") (pinfunction "1_1") (pintype "passive"))
      (node (ref "R84") (pin "1") (pinfunction "1_1") (pintype "passive"))
      (node (ref "TP29") (pin "1") (pinfunction "1_1") (pintype "passive"))
      (node (ref "U7") (pin "3") (pinfunction "IN_3") (pintype "power_in"))
    )
    (net (code "4") (name "+5V_R") (class "Default")
      (node (ref "C21") (pin "2") (pinfunction "2_2") (pintype "passive"))
      (node (ref "C24") (pin "2") (pinfunction "2_2") (pintype "passive"))
      (node (ref "C25") (pin "2") (pinfunction "2_2") (pintype "passive"))
      (node (ref "C26") (pin "2") (pinfunction "2_2") (pintype "passive"))
      (node (ref "C27") (pin "2") (pinfunction "2_2") (pintype "passive"))
      (node (ref "C28") (pin "2") (pinfunction "2_2") (pintype "passive"))
      (node (ref "C29") (pin "2") (pinfunction "2_2") (pintype "passive"))
      (node (ref "D7") (pin "2") (pinfunction "A_2") (pintype "passive"))
      (node (ref "L1") (pin "2") (pinfunction "2_2") (pintype "passive"))
      (node (ref "MD2") (pin "4") (pinfunction "VOUT_4") (pintype "power_in"))
      (node (ref "MD2") (pin "5") (pinfunction "Sense_5") (pintype "passive"))
      (node (ref "R42") (pin "2") (pinfunction "2_2") (pintype "passive"))
      (node (ref "R82") (pin "1") (pinfunction "1_1") (pintype "passive"))
      (node (ref "R83") (pin "2") (pinfunction "2_2") (pintype "passive"))
    )
    (net (code "5") (name "+12V0") (class "Default")
      (node (ref "C14") (pin "2") (pinfunction "2_2") (pintype "passive"))
      (node (ref "C15") (pin "2") (pinfunction "2_2") (pintype "passive"))
      (node (ref "C16") (pin "2") (pinfunction "2_2") (pintype "passive"))
      (node (ref "C17") (pin "2") (pinfunction "2_2") (pintype "passive"))
      (node (ref "C18") (pin "2") (pinfunction "2_2") (pintype "passive"))
      (node (ref "C57") (pin "2") (pinfunction "2_2") (pintype "passive"))
      (node (ref "C58") (pin "2") (pinfunction "2_2") (pintype "passive"))
      (node (ref "C59") (pin "2") (pinfunction "2_2") (pintype "passive"))
      (node (ref "MD2") (pin "2") (pinfunction "VIN_2") (pintype "power_in"))
      (node (ref "Q10") (pin "2") (pinfunction "S_2") (pintype "passive"))
      (node (ref "R46") (pin "1") (pinfunction "1_1") (pintype "passive"))
      (node (ref "R48") (pin "2") (pinfunction "2_2") (pintype "passive"))
      (node (ref "R58") (pin "2") (pinfunction "2_2") (pintype "passive"))
      (node (ref "U3") (pin "11") (pinfunction "VIN_11") (pintype "power_in"))
      (node (ref "U3") (pin "2") (pinfunction "VIN_2") (pintype "power_in"))
      (node (ref "U5") (pin "25") (pinfunction "VOUT_25") (pintype "power_in"))
      (node (ref "U5") (pin "26") (pinfunction "VOUT_26") (pintype "power_in"))
      (node (ref "U5") (pin "27") (pinfunction "VOUT_27") (pintype "power_in"))
      (node (ref "U5") (pin "28") (pinfunction "VOUT_28") (pintype "power_in"))
      (node (ref "U5") (pin "29") (pinfunction "VOUT_29") (pintype "power_in"))
      (node (ref "U5") (pin "30") (pinfunction "VOUT_30") (pintype "power_in"))
      (node (ref "U5") (pin "31") (pinfunction "VOUT_31") (pintype "power_in"))
      (node (ref "U5") (pin "32") (pinfunction "VOUT_32") (pintype "power_in"))
    )
    (net (code "6") (name "+12_R") (class "Default")
      (node (ref "R57") (pin "2") (pinfunction "2_2") (pintype "passive"))
      (node (ref "U5") (pin "10") (pinfunction "VIN_10") (pintype "power_in"))
      (node (ref "U5") (pin "11") (pinfunction "VIN_11") (pintype "power_in"))
      (node (ref "U5") (pin "12") (pinfunction "VIN_12") (pintype "power_in"))
      (node (ref "U5") (pin "13") (pinfunction "VIN_13") (pintype "power_in"))
      (node (ref "U5") (pin "14") (pinfunction "VIN_14") (pintype "power_in"))
      (node (ref "U5") (pin "15") (pinfunction "VIN_15") (pintype "power_in"))
      (node (ref "U5") (pin "16") (pinfunction "VIN_16") (pintype "power_in"))
      (node (ref "U5") (pin "33") (pinfunction "(VIN_)_33") (pintype "power_in"))
      (node (ref "U5") (pin "9") (pinfunction "VIN_9") (pintype "power_in"))
    )
    (net (code "7") (name "/5VREGEN") (class "Default")
      (node (ref "MD2") (pin "1") (pinfunction "On/Off_Control_1") (pintype "input"))
      (node (ref "S5") (pin "2") (pinfunction "COM_2") (pintype "passive"))
      (node (ref "U3") (pin "15") (pinfunction "EN_15") (pintype "input"))
    )
    (net (code "8") (name "/EN_5V") (class "Default")
      (node (ref "Q13") (pin "1") (pinfunction "G_1") (pintype "passive"))
      (node (ref "S7") (pin "2") (pinfunction "COM_2") (pintype "passive"))
      (node (ref "TP23") (pin "1") (pinfunction "1_1") (pintype "passive"))
      (node (ref "U5") (pin "4") (pinfunction "ON/PD_4") (pintype "passive"))
    )
    (net (code "9") (name "/GOK_5V") (class "Default")
      (node (ref "Q11") (pin "1") (pinfunction "G_1") (pintype "passive"))
      (node (ref "R68") (pin "1") (pinfunction "1_1") (pintype "passive"))
      (node (ref "TP25") (pin "1") (pinfunction "1_1") (pintype "passive"))
      (node (ref "U5") (pin "5") (pinfunction "GOK_5") (pintype "passive"))
    )
    (net (code "10") (name "/Imon_5V") (class "Default")
      (node (ref "C30") (pin "2") (pinfunction "2_2") (pintype "passive"))
      (node (ref "R56") (pin "2") (pinfunction "2_2") (pintype "passive"))
      (node (ref "TP21") (pin "1") (pinfunction "1_1") (pintype "passive"))
      (node (ref "U5") (pin "22") (pinfunction "IMON_22") (pintype "passive"))
    )
    (net (code "11") (name "/MCU_SCL0") (class "Default")
      (node (ref "R43") (pin "2") (pinfunction "2_2") (pintype "passive"))
      (node (ref "R59") (pin "2") (pinfunction "2_2") (pintype "passive"))
      (node (ref "R75") (pin "2") (pinfunction "2_2") (pintype "passive"))
      (node (ref "R80") (pin "2") (pinfunction "2_2") (pintype "passive"))
      (node (ref "U4") (pin "5") (pinfunction "SCL_5") (pintype "input"))
      (node (ref "U6") (pin "5") (pinfunction "SCL_5") (pintype "input"))
      (node (ref "U8") (pin "5") (pinfunction "SCL_5") (pintype "input"))
      (node (ref "U9") (pin "5") (pinfunction "SCL_5") (pintype "input"))
    )
    (net (code "12") (name "/MCU_SDA0") (class "Default")
      (node (ref "R44") (pin "2") (pinfunction "2_2") (pintype "passive"))
      (node (ref "R60") (pin "2") (pinfunction "2_2") (pintype "passive"))
      (node (ref "R76") (pin "2") (pinfunction "2_2") (pintype "passive"))
      (node (ref "R81") (pin "2") (pinfunction "2_2") (pintype "passive"))
      (node (ref "U4") (pin "6") (pinfunction "SDA_6") (pintype "bidirectional"))
      (node (ref "U6") (pin "6") (pinfunction "SDA_6") (pintype "bidirectional"))
      (node (ref "U8") (pin "6") (pinfunction "SDA_6") (pintype "bidirectional"))
      (node (ref "U9") (pin "6") (pinfunction "SDA_6") (pintype "bidirectional"))
    )
    (net (code "13") (name "/OC_5V") (class "Default")
      (node (ref "Q12") (pin "1") (pinfunction "G_1") (pintype "passive"))
      (node (ref "R69") (pin "1") (pinfunction "1_1") (pintype "passive"))
      (node (ref "TP24") (pin "1") (pinfunction "1_1") (pintype "passive"))
      (node (ref "U5") (pin "3") (pinfunction "D_OC_3") (pintype "passive"))
    )
    (net (code "14") (name "/PGOOD_5V") (class "Default")
      (node (ref "MD2") (pin "10") (pinfunction "Power_Good_Out_10") (pintype "open_collector"))
      (node (ref "Q10") (pin "1") (pinfunction "G_1") (pintype "passive"))
      (node (ref "R58") (pin "1") (pinfunction "1_1") (pintype "passive"))
    )
    (net (code "15") (name "/VDD_5V") (class "Default")
      (node (ref "C31") (pin "2") (pinfunction "2_2") (pintype "passive"))
      (node (ref "SW3") (pin "2") (pinfunction "2_2") (pintype "passive"))
      (node (ref "SW3") (pin "3") (pinfunction "2_3") (pintype "passive"))
      (node (ref "U5") (pin "21") (pinfunction "VDD_21") (pintype "power_in"))
    )
    (net (code "16") (name "/VO_Lighting") (class "Default")
      (node (ref "R62") (pin "1") (pinfunction "1_1") (pintype "passive"))
      (node (ref "R65") (pin "1") (pinfunction "1_1") (pintype "passive"))
      (node (ref "TP27") (pin "1") (pinfunction "1_1") (pintype "passive"))
    )
    (net (code "17") (name "/VO_Teacher_Arms") (class "Default")
      (node (ref "R48") (pin "1") (pinfunction "1_1") (pintype "passive"))
      (node (ref "R54") (pin "1") (pinfunction "1_1") (pintype "passive"))
      (node (ref "TP26") (pin "1") (pinfunction "1_1") (pintype "passive"))
    )
    (net (code "18") (name "/Vtemp_5V") (class "Default")
      (node (ref "C33") (pin "2") (pinfunction "2_2") (pintype "passive"))
      (node (ref "TP22") (pin "1") (pinfunction "1_1") (pintype "passive"))
      (node (ref "U5") (pin "18") (pinfunction "VTEMP_18") (pintype "passive"))
    )
    (net (code "19") (name "GND") (class "Default")
      (node (ref "C14") (pin "1") (pinfunction "1_1") (pintype "passive"))
      (node (ref "C15") (pin "1") (pinfunction "1_1") (pintype "passive"))
      (node (ref "C16") (pin "1") (pinfunction "1_1") (pintype "passive"))
      (node (ref "C17") (pin "1") (pinfunction "1_1") (pintype "passive"))
      (node (ref "C18") (pin "1") (pinfunction "1_1") (pintype "passive"))
      (node (ref "C19") (pin "1") (pinfunction "1_1") (pintype "passive"))
      (node (ref "C20") (pin "1") (pinfunction "1_1") (pintype "passive"))
      (node (ref "C23") (pin "1") (pinfunction "1_1") (pintype "passive"))
      (node (ref "C24") (pin "1") (pinfunction "1_1") (pintype "passive"))
      (node (ref "C25") (pin "1") (pinfunction "1_1") (pintype "passive"))
      (node (ref "C26") (pin "1") (pinfunction "1_1") (pintype "passive"))
      (node (ref "C27") (pin "1") (pinfunction "1_1") (pintype "passive"))
      (node (ref "C28") (pin "1") (pinfunction "1_1") (pintype "passive"))
      (node (ref "C29") (pin "1") (pinfunction "1_1") (pintype "passive"))
      (node (ref "C30") (pin "1") (pinfunction "1_1") (pintype "passive"))
      (node (ref "C31") (pin "1") (pinfunction "1_1") (pintype "passive"))
      (node (ref "C32") (pin "1") (pinfunction "1_1") (pintype "passive"))
      (node (ref "C33") (pin "1") (pinfunction "1_1") (pintype "passive"))
      (node (ref "C34") (pin "1") (pinfunction "1_1") (pintype "passive"))
      (node (ref "C35") (pin "1") (pinfunction "1_1") (pintype "passive"))
      (node (ref "C36") (pin "1") (pinfunction "1_1") (pintype "passive"))
      (node (ref "C37") (pin "1") (pinfunction "1_1") (pintype "passive"))
      (node (ref "C39") (pin "1") (pinfunction "1_1") (pintype "passive"))
      (node (ref "C40") (pin "1") (pinfunction "1_1") (pintype "passive"))
      (node (ref "C41") (pin "1") (pinfunction "1_1") (pintype "passive"))
      (node (ref "C42") (pin "1") (pinfunction "1_1") (pintype "passive"))
      (node (ref "C44") (pin "1") (pinfunction "1_1") (pintype "passive"))
      (node (ref "C45") (pin "1") (pinfunction "1_1") (pintype "passive"))
      (node (ref "C57") (pin "1") (pinfunction "1_1") (pintype "passive"))
      (node (ref "C58") (pin "1") (pinfunction "1_1") (pintype "passive"))
      (node (ref "C59") (pin "1") (pinfunction "1_1") (pintype "passive"))
      (node (ref "J11") (pin "2") (pinfunction "2_2") (pintype "passive"))
      (node (ref "J12") (pin "2") (pinfunction "2_2") (pintype "passive"))
      (node (ref "J15") (pin "2") (pinfunction "2_2") (pintype "passive"))
      (node (ref "J16") (pin "2") (pinfunction "2_2") (pintype "passive"))
      (node (ref "J3") (pin "2") (pinfunction "2_2") (pintype "passive"))
      (node (ref "J4") (pin "2") (pinfunction "2_2") (pintype "passive"))
      (node (ref "J7") (pin "2") (pinfunction "2_2") (pintype "passive"))
      (node (ref "J8") (pin "2") (pinfunction "2_2") (pintype "passive"))
      (node (ref "MD2") (pin "3") (pinfunction "Ground_3") (pintype "power_in"))
      (node (ref "MD2") (pin "7") (pinfunction "Ground_7") (pintype "power_in"))
      (node (ref "Q13") (pin "2") (pinfunction "S_2") (pintype "passive"))
      (node (ref "R41") (pin "1") (pinfunction "1_1") (pintype "passive"))
      (node (ref "R47") (pin "1") (pinfunction "1_1") (pintype "passive"))
      (node (ref "R50") (pin "1") (pinfunction "1_1") (pintype "passive"))
      (node (ref "R53") (pin "1") (pinfunction "1_1") (pintype "passive"))
      (node (ref "R55") (pin "2") (pinfunction "2_2") (pintype "passive"))
      (node (ref "R56") (pin "1") (pinfunction "1_1") (pintype "passive"))
      (node (ref "R63") (pin "1") (pinfunction "1_1") (pintype "passive"))
      (node (ref "R64") (pin "2") (pinfunction "2_2") (pintype "passive"))
      (node (ref "R67") (pin "1") (pinfunction "1_1") (pintype "passive"))
      (node (ref "R71") (pin "1") (pinfunction "1_1") (pintype "passive"))
      (node (ref "R72") (pin "1") (pinfunction "1_1") (pintype "passive"))
      (node (ref "R74") (pin "2") (pinfunction "2_2") (pintype "passive"))
      (node (ref "S5") (pin "1") (pinfunction "NC_1") (pintype "passive"))
      (node (ref "SW3") (pin "1") (pinfunction "1_1") (pintype "passive"))
      (node (ref "SW3") (pin "4") (pinfunction "1_4") (pintype "passive"))
      (node (ref "U3") (pin "10") (pinfunction "PGND_10") (pintype "power_in"))
      (node (ref "U3") (pin "12") (pinfunction "AGND_12") (pintype "power_in"))
      (node (ref "U3") (pin "3") (pinfunction "PGND_3") (pintype "power_in"))
      (node (ref "U3") (pin "4") (pinfunction "PGND_4") (pintype "power_in"))
      (node (ref "U3") (pin "5") (pinfunction "PGND_5") (pintype "power_in"))
      (node (ref "U3") (pin "8") (pinfunction "PGND_8") (pintype "power_in"))
      (node (ref "U3") (pin "9") (pinfunction "PGND_9") (pintype "power_in"))
      (node (ref "U4") (pin "3") (pinfunction "GND_3") (pintype "power_in"))
      (node (ref "U5") (pin "20") (pinfunction "GND_20") (pintype "power_in"))
      (node (ref "U6") (pin "3") (pinfunction "GND_3") (pintype "power_in"))
      (node (ref "U7") (pin "1") (pinfunction "GND_1") (pintype "power_in"))
      (node (ref "U8") (pin "3") (pinfunction "GND_3") (pintype "power_in"))
      (node (ref "U9") (pin "3") (pinfunction "GND_3") (pintype "power_in"))
    )
    (net (code "20") (name "Net-(C13-Pad1)") (class "Default")
      (node (ref "C13") (pin "1") (pinfunction "1_1") (pintype "passive"))
      (node (ref "L1") (pin "1") (pinfunction "1_1") (pintype "passive"))
      (node (ref "U3") (pin "6") (pinfunction "SW_6") (pintype "power_in"))
      (node (ref "U3") (pin "7") (pinfunction "SW_7") (pintype "power_in"))
    )
    (net (code "21") (name "Net-(D7-K)") (class "Default")
      (node (ref "D7") (pin "1") (pinfunction "K_1") (pintype "passive"))
      (node (ref "R41") (pin "2") (pinfunction "2_2") (pintype "passive"))
    )
    (net (code "22") (name "Net-(D8-A)") (class "Default")
      (node (ref "D8") (pin "2") (pinfunction "A_2") (pintype "passive"))
      (node (ref "Q10") (pin "3") (pinfunction "D_3") (pintype "passive"))
    )
    (net (code "23") (name "Net-(D8-K)") (class "Default")
      (node (ref "D8") (pin "1") (pinfunction "K_1") (pintype "passive"))
      (node (ref "R64") (pin "1") (pinfunction "1_1") (pintype "passive"))
    )
    (net (code "24") (name "Net-(D9-K)") (class "Default")
      (node (ref "D9") (pin "1") (pinfunction "K_1") (pintype "passive"))
      (node (ref "R70") (pin "2") (pinfunction "2_2") (pintype "passive"))
    )
    (net (code "25") (name "Net-(D10-A)") (class "Default")
      (node (ref "D10") (pin "2") (pinfunction "A_2") (pintype "passive"))
      (node (ref "Q11") (pin "3") (pinfunction "D_3") (pintype "passive"))
    )
    (net (code "26") (name "Net-(D10-K)") (class "Default")
      (node (ref "D10") (pin "1") (pinfunction "K_1") (pintype "passive"))
      (node (ref "R71") (pin "2") (pinfunction "2_2") (pintype "passive"))
    )
    (net (code "27") (name "Net-(D11-A)") (class "Default")
      (node (ref "D11") (pin "2") (pinfunction "A_2") (pintype "passive"))
      (node (ref "Q12") (pin "3") (pinfunction "D_3") (pintype "passive"))
    )
    (net (code "28") (name "Net-(D11-K)") (class "Default")
      (node (ref "D11") (pin "1") (pinfunction "K_1") (pintype "passive"))
      (node (ref "R72") (pin "2") (pinfunction "2_2") (pintype "passive"))
    )
    (net (code "29") (name "Net-(D12-K)") (class "Default")
      (node (ref "D12") (pin "1") (pinfunction "K_1") (pintype "passive"))
      (node (ref "R74") (pin "1") (pinfunction "1_1") (pintype "passive"))
    )
    (net (code "30") (name "Net-(MD2-Trim)") (class "Default")
      (node (ref "MD2") (pin "6") (pinfunction "Trim_6") (pintype "passive"))
      (node (ref "R63") (pin "2") (pinfunction "2_2") (pintype "passive"))
    )
    (net (code "31") (name "Net-(Q13-D)") (class "Default")
      (node (ref "Q13") (pin "3") (pinfunction "D_3") (pintype "passive"))
      (node (ref "R70") (pin "1") (pinfunction "1_1") (pintype "passive"))
    )
    (net (code "32") (name "Net-(S7-NC)") (class "Default")
      (node (ref "R66") (pin "1") (pinfunction "1_1") (pintype "passive"))
      (node (ref "S7") (pin "1") (pinfunction "NC_1") (pintype "passive"))
    )
    (net (code "33") (name "Net-(S7-NO)") (class "Default")
      (node (ref "R67") (pin "2") (pinfunction "2_2") (pintype "passive"))
      (node (ref "S7") (pin "3") (pinfunction "NO_3") (pintype "passive"))
    )
    (net (code "34") (name "Net-(U3-BOOT)") (class "Default")
      (node (ref "C13") (pin "2") (pinfunction "2_2") (pintype "passive"))
      (node (ref "U3") (pin "1") (pinfunction "BOOT_1") (pintype "power_in"))
    )
    (net (code "35") (name "Net-(U3-FB)") (class "Default")
      (node (ref "C21") (pin "1") (pinfunction "1_1") (pintype "passive"))
      (node (ref "R42") (pin "1") (pinfunction "1_1") (pintype "passive"))
      (node (ref "R47") (pin "2") (pinfunction "2_2") (pintype "passive"))
      (node (ref "U3") (pin "13") (pinfunction "FB_13") (pintype "input"))
    )
    (net (code "36") (name "Net-(U3-MODE)") (class "Default")
      (node (ref "R49") (pin "2") (pinfunction "2_2") (pintype "passive"))
      (node (ref "R55") (pin "1") (pinfunction "1_1") (pintype "passive"))
      (node (ref "U3") (pin "18") (pinfunction "MODE_18") (pintype "input"))
    )
    (net (code "37") (name "Net-(U3-PGOOD)") (class "Default")
      (node (ref "R45") (pin "1") (pinfunction "1_1") (pintype "passive"))
      (node (ref "U3") (pin "16") (pinfunction "PGOOD_16") (pintype "open_collector"))
    )
    (net (code "38") (name "Net-(U3-VREG5)") (class "Default")
      (node (ref "C23") (pin "2") (pinfunction "2_2") (pintype "passive"))
      (node (ref "R45") (pin "2") (pinfunction "2_2") (pintype "passive"))
      (node (ref "R49") (pin "1") (pinfunction "1_1") (pintype "passive"))
      (node (ref "U3") (pin "17") (pinfunction "VREG5_17") (pintype "power_in"))
    )
    (net (code "39") (name "Net-(U4-A0)") (class "Default")
      (node (ref "J2") (pin "1") (pinfunction "1_1") (pintype "passive"))
      (node (ref "J4") (pin "1") (pinfunction "1_1") (pintype "passive"))
      (node (ref "U4") (pin "7") (pinfunction "A0_7") (pintype "input"))
    )
    (net (code "40") (name "Net-(U4-A1)") (class "Default")
      (node (ref "J1") (pin "1") (pinfunction "1_1") (pintype "passive"))
      (node (ref "J3") (pin "1") (pinfunction "1_1") (pintype "passive"))
      (node (ref "U4") (pin "8") (pinfunction "A1_8") (pintype "input"))
    )
    (net (code "41") (name "Net-(U4-IN+)") (class "Default")
      (node (ref "C22") (pin "2") (pinfunction "2_2") (pintype "passive"))
      (node (ref "R46") (pin "2") (pinfunction "2_2") (pintype "passive"))
      (node (ref "U4") (pin "1") (pinfunction "IN+_1") (pintype "passive"))
    )
    (net (code "42") (name "Net-(U4-IN-)") (class "Default")
      (node (ref "C22") (pin "1") (pinfunction "1_1") (pintype "passive"))
      (node (ref "R54") (pin "2") (pinfunction "2_2") (pintype "passive"))
      (node (ref "U4") (pin "2") (pinfunction "IN-_2") (pintype "input"))
    )
    (net (code "43") (name "Net-(U5A-CLREF)") (class "Default")
      (node (ref "R53") (pin "2") (pinfunction "2_2") (pintype "passive"))
      (node (ref "U5") (pin "24") (pinfunction "CLREF_24") (pintype "passive"))
    )
    (net (code "44") (name "Net-(U5A-CS)") (class "Default")
      (node (ref "R50") (pin "2") (pinfunction "2_2") (pintype "passive"))
      (node (ref "U5") (pin "23") (pinfunction "CS_23") (pintype "passive"))
    )
    (net (code "45") (name "Net-(U5A-Gate)") (class "Default")
      (node (ref "C35") (pin "2") (pinfunction "2_2") (pintype "passive"))
      (node (ref "U5") (pin "17") (pinfunction "Gate_17") (pintype "passive"))
    )
    (net (code "46") (name "Net-(U5A-SS)") (class "Default")
      (node (ref "C32") (pin "2") (pinfunction "2_2") (pintype "passive"))
      (node (ref "U5") (pin "19") (pinfunction "SS_19") (pintype "passive"))
    )
    (net (code "47") (name "Net-(U5A-VINF)") (class "Default")
      (node (ref "C34") (pin "2") (pinfunction "2_2") (pintype "passive"))
      (node (ref "R57") (pin "1") (pinfunction "1_1") (pintype "passive"))
      (node (ref "U5") (pin "7") (pinfunction "VINF_7") (pintype "power_in"))
    )
    (net (code "48") (name "Net-(U6-A0)") (class "Default")
      (node (ref "J6") (pin "1") (pinfunction "1_1") (pintype "passive"))
      (node (ref "J8") (pin "1") (pinfunction "1_1") (pintype "passive"))
      (node (ref "U6") (pin "7") (pinfunction "A0_7") (pintype "input"))
    )
    (net (code "49") (name "Net-(U6-A1)") (class "Default")
      (node (ref "J5") (pin "1") (pinfunction "1_1") (pintype "passive"))
      (node (ref "J7") (pin "1") (pinfunction "1_1") (pintype "passive"))
      (node (ref "U6") (pin "8") (pinfunction "A1_8") (pintype "input"))
    )
    (net (code "50") (name "Net-(U6-IN+)") (class "Default")
      (node (ref "C38") (pin "2") (pinfunction "2_2") (pintype "passive"))
      (node (ref "R61") (pin "2") (pinfunction "2_2") (pintype "passive"))
      (node (ref "U6") (pin "1") (pinfunction "IN+_1") (pintype "passive"))
    )
    (net (code "51") (name "Net-(U6-IN-)") (class "Default")
      (node (ref "C38") (pin "1") (pinfunction "1_1") (pintype "passive"))
      (node (ref "R65") (pin "2") (pinfunction "2_2") (pintype "passive"))
      (node (ref "U6") (pin "2") (pinfunction "IN-_2") (pintype "input"))
    )
    (net (code "52") (name "Net-(U8-A0)") (class "Default")
      (node (ref "J10") (pin "1") (pinfunction "1_1") (pintype "passive"))
      (node (ref "J12") (pin "1") (pinfunction "1_1") (pintype "passive"))
      (node (ref "U8") (pin "7") (pinfunction "A0_7") (pintype "input"))
    )
    (net (code "53") (name "Net-(U8-A1)") (class "Default")
      (node (ref "J11") (pin "1") (pinfunction "1_1") (pintype "passive"))
      (node (ref "J9") (pin "1") (pinfunction "1_1") (pintype "passive"))
      (node (ref "U8") (pin "8") (pinfunction "A1_8") (pintype "input"))
    )
    (net (code "54") (name "Net-(U8-IN+)") (class "Default")
      (node (ref "C43") (pin "2") (pinfunction "2_2") (pintype "passive"))
      (node (ref "R77") (pin "2") (pinfunction "2_2") (pintype "passive"))
      (node (ref "U8") (pin "1") (pinfunction "IN+_1") (pintype "passive"))
    )
    (net (code "55") (name "Net-(U8-IN-)") (class "Default")
      (node (ref "C43") (pin "1") (pinfunction "1_1") (pintype "passive"))
      (node (ref "R79") (pin "2") (pinfunction "2_2") (pintype "passive"))
      (node (ref "U8") (pin "2") (pinfunction "IN-_2") (pintype "input"))
    )
    (net (code "56") (name "Net-(U9-A0)") (class "Default")
      (node (ref "J14") (pin "1") (pinfunction "1_1") (pintype "passive"))
      (node (ref "J16") (pin "1") (pinfunction "1_1") (pintype "passive"))
      (node (ref "U9") (pin "7") (pinfunction "A0_7") (pintype "input"))
    )
    (net (code "57") (name "Net-(U9-A1)") (class "Default")
      (node (ref "J13") (pin "1") (pinfunction "1_1") (pintype "passive"))
      (node (ref "J15") (pin "1") (pinfunction "1_1") (pintype "passive"))
      (node (ref "U9") (pin "8") (pinfunction "A1_8") (pintype "input"))
    )
    (net (code "58") (name "Net-(U9-IN+)") (class "Default")
      (node (ref "C46") (pin "2") (pinfunction "2_2") (pintype "passive"))
      (node (ref "R82") (pin "2") (pinfunction "2_2") (pintype "passive"))
      (node (ref "U9") (pin "1") (pinfunction "IN+_1") (pintype "passive"))
    )
    (net (code "59") (name "Net-(U9-IN-)") (class "Default")
      (node (ref "C46") (pin "1") (pinfunction "1_1") (pintype "passive"))
      (node (ref "R84") (pin "2") (pinfunction "2_2") (pintype "passive"))
      (node (ref "U9") (pin "2") (pinfunction "IN-_2") (pintype "input"))
    )
    (net (code "60") (name "unconnected-(MD2-NC-Pad8)") (class "Default")
      (node (ref "MD2") (pin "8") (pinfunction "NC_8") (pintype "passive+no_connect"))
    )
    (net (code "61") (name "unconnected-(MD2-NC-Pad9)") (class "Default")
      (node (ref "MD2") (pin "9") (pinfunction "NC_9") (pintype "passive+no_connect"))
    )
    (net (code "62") (name "unconnected-(MD2-NC-Pad11)") (class "Default")
      (node (ref "MD2") (pin "11") (pinfunction "NC_11") (pintype "passive+no_connect"))
    )
    (net (code "63") (name "unconnected-(MD2-NC-Pad12)") (class "Default")
      (node (ref "MD2") (pin "12") (pinfunction "NC_12") (pintype "passive+no_connect"))
    )
    (net (code "64") (name "unconnected-(S5-NO-Pad3)") (class "Default")
      (node (ref "S5") (pin "3") (pinfunction "NO_3") (pintype "passive+no_connect"))
    )
    (net (code "65") (name "unconnected-(U3-SS-Pad14)") (class "Default")
      (node (ref "U3") (pin "14") (pinfunction "SS_14") (pintype "output+no_connect"))
    )
    (net (code "66") (name "unconnected-(U5A-NC-Pad1)") (class "Default")
      (node (ref "U5") (pin "1") (pinfunction "NC_1") (pintype "passive+no_connect"))
    )
    (net (code "67") (name "unconnected-(U5A-NC-Pad2)") (class "Default")
      (node (ref "U5") (pin "2") (pinfunction "NC_2") (pintype "passive+no_connect"))
    )
    (net (code "68") (name "unconnected-(U5A-NC-Pad6)") (class "Default")
      (node (ref "U5") (pin "6") (pinfunction "NC_6") (pintype "passive+no_connect"))
    )
    (net (code "69") (name "unconnected-(U5A-NC-Pad8)") (class "Default")
      (node (ref "U5") (pin "8") (pinfunction "NC_8") (pintype "passive+no_connect"))
    )
  )
)
